# MergeRev3_0.net
KiCad netlist of a schematic drawn in Altium Designer
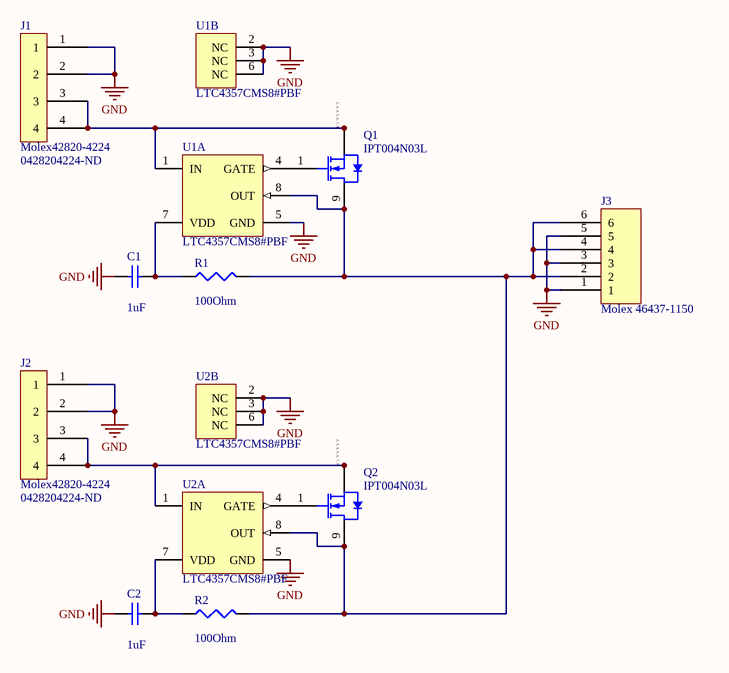
[diagram p0: MergeRev3_0.SchDoc]

(export (version "E")
  (design (tool "Eeschema 10.0.6"))
  (components
    (comp (ref "C1")
      (value "1uF")
      (footprint "C1206")
      (description "Capacitor (Semiconductor SIM Model)")
      (fields (field (name "Comment") "Cap Semi") (field (name "PUBLISHER") "Altium Limited"))
      (libsource (lib "Miscellaneous Devices") (part "Cap Semi"))
    )
    (comp (ref "C2")
      (value "1uF")
      (footprint "C1206")
      (description "Capacitor (Semiconductor SIM Model)")
      (fields (field (name "Comment") "Cap Semi") (field (name "PUBLISHER") "Altium Limited"))
      (libsource (lib "Miscellaneous Devices") (part "Cap Semi"))
    )
    (comp (ref "J1")
      (value "Molex42820-4224")
      (footprint "Molex42820-4224")
      (fields (field (name "SUPPLIER PART NUMBER 1") "0428204224-ND"))
      (libsource (lib "Molex42820-4224") (part "Molex42820-4224"))
    )
    (comp (ref "J2")
      (value "Molex42820-4224")
      (footprint "Molex42820-4224")
      (fields (field (name "SUPPLIER PART NUMBER 1") "0428204224-ND"))
      (libsource (lib "Molex42820-4224") (part "Molex42820-4224"))
    )
    (comp (ref "J3")
      (value "Molex 46437-1150")
      (footprint "Molex 46437-1150")
      (description "5.50mm Pitch EXTreme Ten60Power Right Angle Plug Assembly with Guide Pins, 6 DC Power Circuits")
      (libsource (lib "Molex46437-1150") (part "Molex 46437-1150"))
    )
    (comp (ref "Q1")
      (value "IPT004N03L")
      (footprint "INF-PG-HSOF-8-1_V")
      (description "N-Channel OptiMOS(TM) Power-MOSFET, 30 V VDS, 300 A ID, -55 to 175 degC, PG-HSOF-8, Reel, Green")
      (fields (field (name "MANUFACTURER") "Infineon"))
      (libsource (lib "MergeRev3_0") (part "IPT004N03L"))
    )
    (comp (ref "Q2")
      (value "IPT004N03L")
      (footprint "INF-PG-HSOF-8-1_V")
      (description "N-Channel OptiMOS(TM) Power-MOSFET, 30 V VDS, 300 A ID, -55 to 175 degC, PG-HSOF-8, Reel, Green")
      (fields (field (name "MANUFACTURER") "Infineon"))
      (libsource (lib "MergeRev3_0") (part "IPT004N03L"))
    )
    (comp (ref "R1")
      (value "100Ohm")
      (footprint "J1-0603")
      (description "Resistor")
      (fields (field (name "Comment") "Res3") (field (name "PUBLISHER") "Altium Limited"))
      (libsource (lib "Miscellaneous Devices") (part "Res3"))
    )
    (comp (ref "R2")
      (value "100Ohm")
      (footprint "J1-0603")
      (description "Resistor")
      (fields (field (name "Comment") "Res3") (field (name "PUBLISHER") "Altium Limited"))
      (libsource (lib "Miscellaneous Devices") (part "Res3"))
    )
    (comp (ref "U1")
      (value "LTC4357CMS8#PBF")
      (footprint "LT-MS8-8_N")
      (fields (field (name "MANUFACTURER") "Linear Technology"))
      (libsource (lib "MergeRev3_0") (part "LTC4357CMS8#PBF"))
    )
    (comp (ref "U2")
      (value "LTC4357CMS8#PBF")
      (footprint "LT-MS8-8_N")
      (fields (field (name "MANUFACTURER") "Linear Technology"))
      (libsource (lib "Merge2") (part "LTC4357CMS8#PBF"))
    )
  )
  (nets
    (net (code "1") (name "GND") (class "Default")
      (node (ref "C1") (pin "1") (pinfunction "1_1") (pintype "passive"))
      (node (ref "C2") (pin "1") (pinfunction "1_1") (pintype "passive"))
      (node (ref "J1") (pin "1") (pinfunction "1_1") (pintype "power_in"))
      (node (ref "J1") (pin "2") (pinfunction "2_2") (pintype "power_in"))
      (node (ref "J2") (pin "1") (pinfunction "1_1") (pintype "power_in"))
      (node (ref "J2") (pin "2") (pinfunction "2_2") (pintype "power_in"))
      (node (ref "J3") (pin "1") (pinfunction "1_1") (pintype "passive"))
      (node (ref "J3") (pin "3") (pinfunction "3_3") (pintype "passive"))
      (node (ref "J3") (pin "5") (pinfunction "5_5") (pintype "passive"))
      (node (ref "U1") (pin "2") (pinfunction "NC_2") (pintype "passive"))
      (node (ref "U1") (pin "3") (pinfunction "NC_3") (pintype "passive"))
      (node (ref "U1") (pin "5") (pinfunction "GND_5") (pintype "power_in"))
      (node (ref "U1") (pin "6") (pinfunction "NC_6") (pintype "passive"))
      (node (ref "U2") (pin "2") (pinfunction "NC_2") (pintype "passive"))
      (node (ref "U2") (pin "3") (pinfunction "NC_3") (pintype "passive"))
      (node (ref "U2") (pin "5") (pinfunction "GND_5") (pintype "power_in"))
      (node (ref "U2") (pin "6") (pinfunction "NC_6") (pintype "passive"))
    )
    (net (code "2") (name "Net-(Q1-D)") (class "Default")
      (node (ref "J3") (pin "2") (pinfunction "2_2") (pintype "passive"))
      (node (ref "J3") (pin "4") (pinfunction "4_4") (pintype "passive"))
      (node (ref "J3") (pin "6") (pinfunction "6_6") (pintype "passive"))
      (node (ref "Q1") (pin "9") (pinfunction "D_9") (pintype "passive"))
      (node (ref "Q2") (pin "9") (pinfunction "D_9") (pintype "passive"))
      (node (ref "R1") (pin "2") (pinfunction "2_2") (pintype "passive"))
      (node (ref "R2") (pin "2") (pinfunction "2_2") (pintype "passive"))
      (node (ref "U1") (pin "8") (pinfunction "OUT_8") (pintype "input"))
      (node (ref "U2") (pin "8") (pinfunction "OUT_8") (pintype "input"))
    )
    (net (code "3") (name "Net-(Q1-GATE)") (class "Default")
      (node (ref "Q1") (pin "1") (pinfunction "GATE_1") (pintype "passive"))
      (node (ref "U1") (pin "4") (pinfunction "GATE_4") (pintype "output"))
    )
    (net (code "4") (name "Net-(Q2-GATE)") (class "Default")
      (node (ref "Q2") (pin "1") (pinfunction "GATE_1") (pintype "passive"))
      (node (ref "U2") (pin "4") (pinfunction "GATE_4") (pintype "output"))
    )
    (net (code "5") (name "Net-(U1A-IN)") (class "Default")
      (node (ref "J1") (pin "3") (pinfunction "3_3") (pintype "power_in"))
      (node (ref "J1") (pin "4") (pinfunction "4_4") (pintype "power_in"))
      (node (ref "Q1") (pin "2") (pinfunction "S_2") (pintype "passive"))
      (node (ref "Q1") (pin "3") (pinfunction "S_3") (pintype "passive"))
      (node (ref "Q1") (pin "4") (pinfunction "S_4") (pintype "passive"))
      (node (ref "Q1") (pin "5") (pinfunction "S_5") (pintype "passive"))
      (node (ref "Q1") (pin "6") (pinfunction "S_6") (pintype "passive"))
      (node (ref "Q1") (pin "7") (pinfunction "S_7") (pintype "passive"))
      (node (ref "Q1") (pin "8") (pinfunction "S_8") (pintype "passive"))
      (node (ref "U1") (pin "1") (pinfunction "IN_1") (pintype "power_in"))
    )
    (net (code "6") (name "Net-(U1A-VDD)") (class "Default")
      (node (ref "C1") (pin "2") (pinfunction "2_2") (pintype "passive"))
      (node (ref "R1") (pin "1") (pinfunction "1_1") (pintype "passive"))
      (node (ref "U1") (pin "7") (pinfunction "VDD_7") (pintype "power_in"))
    )
    (net (code "7") (name "Net-(U2A-IN)") (class "Default")
      (node (ref "J2") (pin "3") (pinfunction "3_3") (pintype "power_in"))
      (node (ref "J2") (pin "4") (pinfunction "4_4") (pintype "power_in"))
      (node (ref "Q2") (pin "2") (pinfunction "S_2") (pintype "passive"))
      (node (ref "Q2") (pin "3") (pinfunction "S_3") (pintype "passive"))
      (node (ref "Q2") (pin "4") (pinfunction "S_4") (pintype "passive"))
      (node (ref "Q2") (pin "5") (pinfunction "S_5") (pintype "passive"))
      (node (ref "Q2") (pin "6") (pinfunction "S_6") (pintype "passive"))
      (node (ref "Q2") (pin "7") (pinfunction "S_7") (pintype "passive"))
      (node (ref "Q2") (pin "8") (pinfunction "S_8") (pintype "passive"))
      (node (ref "U2") (pin "1") (pinfunction "IN_1") (pintype "power_in"))
    )
    (net (code "8") (name "Net-(U2A-VDD)") (class "Default")
      (node (ref "C2") (pin "2") (pinfunction "2_2") (pintype "passive"))
      (node (ref "R2") (pin "1") (pinfunction "1_1") (pintype "passive"))
      (node (ref "U2") (pin "7") (pinfunction "VDD_7") (pintype "power_in"))
    )
  )
)
